# CLRC66302HN_151.net
KiCad netlist of a schematic drawn in Altium Designer
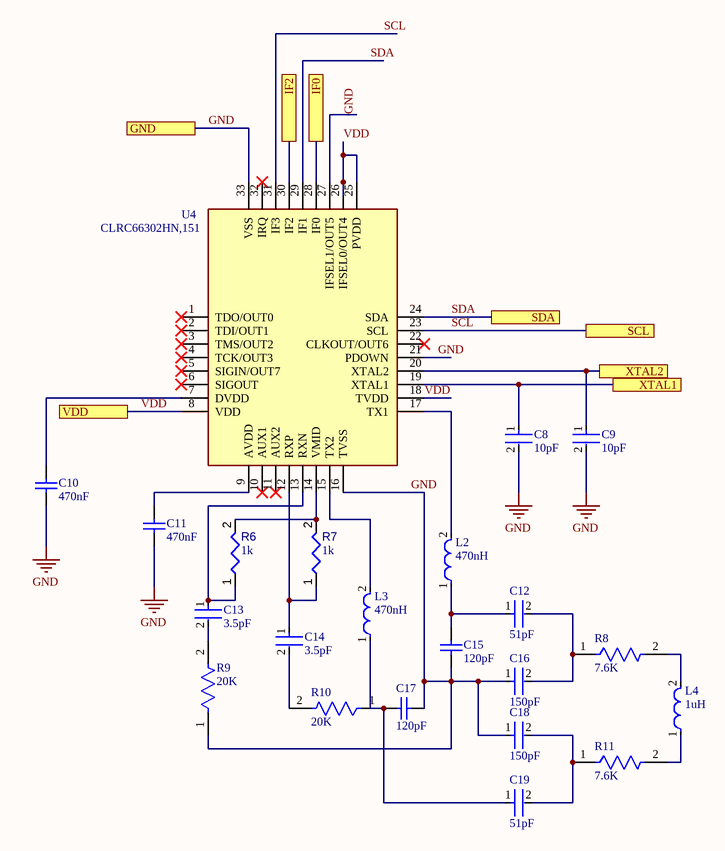
[diagram p0: CLRC66302HN, 151.SchDoc]

(export (version "E")
  (design (tool "Eeschema 10.0.6"))
  (components
    (comp (ref "C8")
      (value "10pF")
      (footprint "FP-GRM033-0_03-IPC_A")
      (description "Chip Multilayer Ceramic Capacitors for General Purpose, 0201, 10pF, C0G, 30ppm/°C, 5%, 25V")
      (fields (field (name "TOLERANCE") "5%"))
      (libsource (lib "Altium Content Vault") (part "b4654b650e69147ec39a6b967a45e02"))
    )
    (comp (ref "C9")
      (value "10pF")
      (footprint "FP-GRM033-0_03-IPC_A")
      (description "Chip Multilayer Ceramic Capacitors for General Purpose, 0201, 10pF, C0G, 30ppm/°C, 5%, 25V")
      (fields (field (name "TOLERANCE") "5%"))
      (libsource (lib "Altium Content Vault") (part "b4654b650e69147ec39a6b967a45e02"))
    )
    (comp (ref "C10")
      (value "470nF")
      (footprint "CAPC1005X55X25LL05T10")
      (fields (field (name "MANUFACTURER") "Murata") (field (name "PART NUMBER") "GRM155R60J474KE19D"))
      (libsource (lib "Altium Content Vault") (part "CAP"))
    )
    (comp (ref "C11")
      (value "470nF")
      (footprint "CAPC1005X55X25LL05T10")
      (fields (field (name "MANUFACTURER") "Murata") (field (name "PART NUMBER") "GRM155R60J474KE19D"))
      (libsource (lib "Altium Content Vault") (part "CAP"))
    )
    (comp (ref "C12")
      (value "51pF")
      (footprint "FP-GRM033-0_03-IPC_B")
      (description "Chip Multilayer Ceramic Capacitors for General Purpose, 0201, 51pF, C0G, 30ppm/°C, 2%, 50V")
      (fields (field (name "TOLERANCE") "2%"))
      (libsource (lib "Altium Content Vault") (part "b4654b650e69147ec39a6b967a45e02"))
    )
    (comp (ref "C13")
      (value "3.5pF")
      (footprint "FP-CL1012-IPC_C")
      (description "Cap Ceramic 3.5pF 50V C0G ±0.25pF SMD 0402 +125°C Paper T/R")
      (libsource (lib "Altium Content Vault") (part "b4654b650e69147ec39a6b967a45e02"))
    )
    (comp (ref "C14")
      (value "3.5pF")
      (footprint "FP-CL1012-IPC_C")
      (description "Cap Ceramic 3.5pF 50V C0G ±0.25pF SMD 0402 +125°C Paper T/R")
      (libsource (lib "Altium Content Vault") (part "b4654b650e69147ec39a6b967a45e02"))
    )
    (comp (ref "C15")
      (value "120pF")
      (footprint "CAPC1005X55X25ML05T10")
      (fields (field (name "MANUFACTURER") "Murata") (field (name "PART NUMBER") "GRM1555C1H121JA01D"))
      (libsource (lib "Altium Content Vault") (part "CAP"))
    )
    (comp (ref "C16")
      (value "150pF")
      (footprint "FP-GRM033-0_03-MFG")
      (description "Chip Multilayer Ceramic Capacitors for General Purpose, 0201, 150pF, X7R, 15%, 10%, 25V")
      (fields (field (name "TOLERANCE") "10%"))
      (libsource (lib "Altium Content Vault") (part "b4654b650e69147ec39a6b967a45e02"))
    )
    (comp (ref "C17")
      (value "120pF")
      (footprint "CAPC1005X55X25ML05T10")
      (fields (field (name "MANUFACTURER") "Murata") (field (name "PART NUMBER") "GRM1555C1H121JA01D"))
      (libsource (lib "Altium Content Vault") (part "CAP"))
    )
    (comp (ref "C18")
      (value "150pF")
      (footprint "FP-GRM033-0_03-MFG")
      (description "Chip Multilayer Ceramic Capacitors for General Purpose, 0201, 150pF, X7R, 15%, 10%, 25V")
      (fields (field (name "TOLERANCE") "10%"))
      (libsource (lib "Altium Content Vault") (part "b4654b650e69147ec39a6b967a45e02"))
    )
    (comp (ref "C19")
      (value "51pF")
      (footprint "FP-GRM033-0_03-IPC_B")
      (description "Chip Multilayer Ceramic Capacitors for General Purpose, 0201, 51pF, C0G, 30ppm/°C, 2%, 50V")
      (fields (field (name "TOLERANCE") "2%"))
      (libsource (lib "Altium Content Vault") (part "b4654b650e69147ec39a6b967a45e02"))
    )
    (comp (ref "L2")
      (value "470nH")
      (footprint "FP-MLZ1005-MFG")
      (description "Shielded Multilayer Inductor 470nH ±20% 500mA 260mΩ SMD 0402")
      (fields (field (name "TOLERANCE") "20%"))
      (libsource (lib "Altium Content Vault") (part "725321dda6339637d4d059423bc1c3c"))
    )
    (comp (ref "L3")
      (value "470nH")
      (footprint "FP-MLZ1005-MFG")
      (description "Shielded Multilayer Inductor 470nH ±20% 500mA 260mΩ SMD 0402")
      (fields (field (name "TOLERANCE") "20%"))
      (libsource (lib "Altium Content Vault") (part "725321dda6339637d4d059423bc1c3c"))
    )
    (comp (ref "L4")
      (value "1uH")
      (footprint "FP-MLP1005D-MFG")
      (description "FIXED IND 1UH 500MA 689 MOHM SMD")
      (fields (field (name "TOLERANCE") "20%"))
      (libsource (lib "Altium Content Vault") (part "725321dda6339637d4d059423bc1c3c"))
    )
    (comp (ref "R6")
      (value "1k")
      (footprint "RESC0402(1005)_L")
      (description "1K 0.063W 5% 0402 (1005 Metric)  SMD")
      (fields (field (name "POWER") "63mW") (field (name "TOLERANCE") "5%"))
      (libsource (lib "JCGada") (part "1KR2J"))
    )
    (comp (ref "R7")
      (value "1k")
      (footprint "RESC0402(1005)_L")
      (description "1K 0.063W 5% 0402 (1005 Metric)  SMD")
      (fields (field (name "POWER") "63mW") (field (name "TOLERANCE") "5%"))
      (libsource (lib "JCGada") (part "1KR2J"))
    )
    (comp (ref "R8")
      (value "7.6K")
      (footprint "FP-AC0402-IPC_B")
      (description "RES 7.68kΩ ±1% 0.063W 0402")
      (fields (field (name "TOLERANCE") "1%"))
      (libsource (lib "Altium Content Vault") (part "1029c3af85768c4190bb7ad29bc67b5"))
    )
    (comp (ref "R9")
      (value "20K")
      (footprint "FP-ERJ2RK-MFG")
      (description "RES SMD 20K OHM 1% 1/10W 0402")
      (fields (field (name "TOLERANCE") "1%"))
      (libsource (lib "Altium Content Vault") (part "1029c3af85768c4190bb7ad29bc67b5"))
    )
    (comp (ref "R10")
      (value "20K")
      (footprint "FP-ERJ2RK-MFG")
      (description "RES SMD 20K OHM 1% 1/10W 0402")
      (fields (field (name "TOLERANCE") "1%"))
      (libsource (lib "Altium Content Vault") (part "1029c3af85768c4190bb7ad29bc67b5"))
    )
    (comp (ref "R11")
      (value "7.6K")
      (footprint "FP-AC0402-IPC_B")
      (description "RES 7.68kΩ ±1% 0.063W 0402")
      (fields (field (name "TOLERANCE") "1%"))
      (libsource (lib "Altium Content Vault") (part "1029c3af85768c4190bb7ad29bc67b5"))
    )
    (comp (ref "U4")
      (value "CLRC66302HN,151")
      (footprint "PcbLib1:QFN50P500X500X100-33N-D")
      (description "Integrated Circuit")
      (fields (field (name "MOUSER PART NUMBER") "771-CLRC66302HN151"))
      (libsource (lib "*") (part "CLRC66302HN,151"))
    )
  )
  (nets
    (net (code "1") (name "/IF0") (class "Default")
      (node (ref "U4") (pin "28") (pinfunction "IF0_28") (pintype "passive"))
    )
    (net (code "2") (name "/IF2") (class "Default")
      (node (ref "U4") (pin "30") (pinfunction "IF2_30") (pintype "passive"))
    )
    (net (code "3") (name "/SCL") (class "Default")
      (node (ref "U4") (pin "23") (pinfunction "SCL_23") (pintype "passive"))
      (node (ref "U4") (pin "31") (pinfunction "IF3_31") (pintype "passive"))
    )
    (net (code "4") (name "/SDA") (class "Default")
      (node (ref "U4") (pin "24") (pinfunction "SDA_24") (pintype "passive"))
      (node (ref "U4") (pin "29") (pinfunction "IF1_29") (pintype "passive"))
    )
    (net (code "5") (name "/VDD") (class "Default")
      (node (ref "U4") (pin "18") (pinfunction "TVDD_18") (pintype "passive"))
      (node (ref "U4") (pin "25") (pinfunction "PVDD_25") (pintype "passive"))
      (node (ref "U4") (pin "26") (pinfunction "IFSEL0/OUT4_26") (pintype "passive"))
      (node (ref "U4") (pin "8") (pinfunction "VDD_8") (pintype "passive"))
    )
    (net (code "6") (name "/XTAL1") (class "Default")
      (node (ref "C8") (pin "1") (pinfunction "1_1") (pintype "passive"))
      (node (ref "U4") (pin "19") (pinfunction "XTAL1_19") (pintype "passive"))
    )
    (net (code "7") (name "/XTAL2") (class "Default")
      (node (ref "C9") (pin "1") (pinfunction "1_1") (pintype "passive"))
      (node (ref "U4") (pin "20") (pinfunction "XTAL2_20") (pintype "passive"))
    )
    (net (code "8") (name "GND") (class "Default")
      (node (ref "C10") (pin "1") (pinfunction "1_1") (pintype "passive"))
      (node (ref "C11") (pin "1") (pinfunction "1_1") (pintype "passive"))
      (node (ref "C15") (pin "1") (pinfunction "1_1") (pintype "passive"))
      (node (ref "C16") (pin "1") (pinfunction "1_1") (pintype "passive"))
      (node (ref "C17") (pin "2") (pinfunction "2_2") (pintype "passive"))
      (node (ref "C18") (pin "1") (pinfunction "1_1") (pintype "passive"))
      (node (ref "C8") (pin "2") (pinfunction "2_2") (pintype "passive"))
      (node (ref "C9") (pin "2") (pinfunction "2_2") (pintype "passive"))
      (node (ref "R9") (pin "1") (pinfunction "1_1") (pintype "passive"))
      (node (ref "U4") (pin "16") (pinfunction "TVSS_16") (pintype "passive"))
      (node (ref "U4") (pin "21") (pinfunction "PDOWN_21") (pintype "passive"))
      (node (ref "U4") (pin "27") (pinfunction "IFSEL1/OUT5_27") (pintype "passive"))
      (node (ref "U4") (pin "33") (pinfunction "VSS_33") (pintype "passive"))
    )
    (net (code "9") (name "Net-(C12-Pad1)") (class "Default")
      (node (ref "C12") (pin "1") (pinfunction "1_1") (pintype "passive"))
      (node (ref "C15") (pin "2") (pinfunction "2_2") (pintype "passive"))
      (node (ref "L2") (pin "1") (pinfunction "1_1") (pintype "passive"))
    )
    (net (code "10") (name "Net-(C12-Pad2)") (class "Default")
      (node (ref "C12") (pin "2") (pinfunction "2_2") (pintype "passive"))
      (node (ref "C16") (pin "2") (pinfunction "2_2") (pintype "passive"))
      (node (ref "R8") (pin "1") (pinfunction "1_1") (pintype "passive"))
    )
    (net (code "11") (name "Net-(C13-Pad2)") (class "Default")
      (node (ref "C13") (pin "2") (pinfunction "2_2") (pintype "passive"))
      (node (ref "R9") (pin "2") (pinfunction "2_2") (pintype "passive"))
    )
    (net (code "12") (name "Net-(C14-Pad2)") (class "Default")
      (node (ref "C14") (pin "2") (pinfunction "2_2") (pintype "passive"))
      (node (ref "R10") (pin "2") (pinfunction "2_2") (pintype "passive"))
    )
    (net (code "13") (name "Net-(C17-Pad1)") (class "Default")
      (node (ref "C17") (pin "1") (pinfunction "1_1") (pintype "passive"))
      (node (ref "C19") (pin "1") (pinfunction "1_1") (pintype "passive"))
      (node (ref "L3") (pin "1") (pinfunction "1_1") (pintype "passive"))
      (node (ref "R10") (pin "1") (pinfunction "1_1") (pintype "passive"))
    )
    (net (code "14") (name "Net-(C18-Pad2)") (class "Default")
      (node (ref "C18") (pin "2") (pinfunction "2_2") (pintype "passive"))
      (node (ref "C19") (pin "2") (pinfunction "2_2") (pintype "passive"))
      (node (ref "R11") (pin "1") (pinfunction "1_1") (pintype "passive"))
    )
    (net (code "15") (name "Net-(L4-Pad1)") (class "Default")
      (node (ref "L4") (pin "1") (pinfunction "1_1") (pintype "passive"))
      (node (ref "R11") (pin "2") (pinfunction "2_2") (pintype "passive"))
    )
    (net (code "16") (name "Net-(L4-Pad2)") (class "Default")
      (node (ref "L4") (pin "2") (pinfunction "2_2") (pintype "passive"))
      (node (ref "R8") (pin "2") (pinfunction "2_2") (pintype "passive"))
    )
    (net (code "17") (name "Net-(U4-AVDD)") (class "Default")
      (node (ref "C11") (pin "2") (pinfunction "2_2") (pintype "passive"))
      (node (ref "U4") (pin "9") (pinfunction "AVDD_9") (pintype "passive"))
    )
    (net (code "18") (name "Net-(U4-DVDD)") (class "Default")
      (node (ref "C10") (pin "2") (pinfunction "2_2") (pintype "passive"))
      (node (ref "U4") (pin "7") (pinfunction "DVDD_7") (pintype "passive"))
    )
    (net (code "19") (name "Net-(U4-RXN)") (class "Default")
      (node (ref "C13") (pin "1") (pinfunction "1_1") (pintype "passive"))
      (node (ref "R6") (pin "1") (pinfunction "1_1") (pintype "passive"))
      (node (ref "U4") (pin "13") (pinfunction "RXN_13") (pintype "passive"))
    )
    (net (code "20") (name "Net-(U4-RXP)") (class "Default")
      (node (ref "C14") (pin "1") (pinfunction "1_1") (pintype "passive"))
      (node (ref "R7") (pin "1") (pinfunction "1_1") (pintype "passive"))
      (node (ref "U4") (pin "12") (pinfunction "RXP_12") (pintype "passive"))
    )
    (net (code "21") (name "Net-(U4-TX1)") (class "Default")
      (node (ref "L2") (pin "2") (pinfunction "2_2") (pintype "passive"))
      (node (ref "U4") (pin "17") (pinfunction "TX1_17") (pintype "passive"))
    )
    (net (code "22") (name "Net-(U4-TX2)") (class "Default")
      (node (ref "L3") (pin "2") (pinfunction "2_2") (pintype "passive"))
      (node (ref "U4") (pin "15") (pinfunction "TX2_15") (pintype "passive"))
    )
    (net (code "23") (name "Net-(U4-VMID)") (class "Default")
      (node (ref "R6") (pin "2") (pinfunction "2_2") (pintype "passive"))
      (node (ref "R7") (pin "2") (pinfunction "2_2") (pintype "passive"))
      (node (ref "U4") (pin "14") (pinfunction "VMID_14") (pintype "passive"))
    )
    (net (code "24") (name "unconnected-(U4-AUX1-Pad10)") (class "Default")
      (node (ref "U4") (pin "10") (pinfunction "AUX1_10") (pintype "passive+no_connect"))
    )
    (net (code "25") (name "unconnected-(U4-AUX2-Pad11)") (class "Default")
      (node (ref "U4") (pin "11") (pinfunction "AUX2_11") (pintype "passive+no_connect"))
    )
    (net (code "26") (name "unconnected-(U4-CLKOUT{slash}OUT6-Pad22)") (class "Default")
      (node (ref "U4") (pin "22") (pinfunction "CLKOUT/OUT6_22") (pintype "passive+no_connect"))
    )
    (net (code "27") (name "unconnected-(U4-IRQ-Pad32)") (class "Default")
      (node (ref "U4") (pin "32") (pinfunction "IRQ_32") (pintype "passive+no_connect"))
    )
    (net (code "28") (name "unconnected-(U4-SIGIN{slash}OUT7-Pad5)") (class "Default")
      (node (ref "U4") (pin "5") (pinfunction "SIGIN/OUT7_5") (pintype "passive+no_connect"))
    )
    (net (code "29") (name "unconnected-(U4-SIGOUT-Pad6)") (class "Default")
      (node (ref "U4") (pin "6") (pinfunction "SIGOUT_6") (pintype "passive+no_connect"))
    )
    (net (code "30") (name "unconnected-(U4-TCK{slash}OUT3-Pad4)") (class "Default")
      (node (ref "U4") (pin "4") (pinfunction "TCK/OUT3_4") (pintype "passive+no_connect"))
    )
    (net (code "31") (name "unconnected-(U4-TDI{slash}OUT1-Pad2)") (class "Default")
      (node (ref "U4") (pin "2") (pinfunction "TDI/OUT1_2") (pintype "passive+no_connect"))
    )
    (net (code "32") (name "unconnected-(U4-TDO{slash}OUT0-Pad1)") (class "Default")
      (node (ref "U4") (pin "1") (pinfunction "TDO/OUT0_1") (pintype "passive+no_connect"))
    )
    (net (code "33") (name "unconnected-(U4-TMS{slash}OUT2-Pad3)") (class "Default")
      (node (ref "U4") (pin "3") (pinfunction "TMS/OUT2_3") (pintype "passive+no_connect"))
    )
  )
)
